# WS2812B.net
KiCad netlist of a schematic drawn in EAGLE
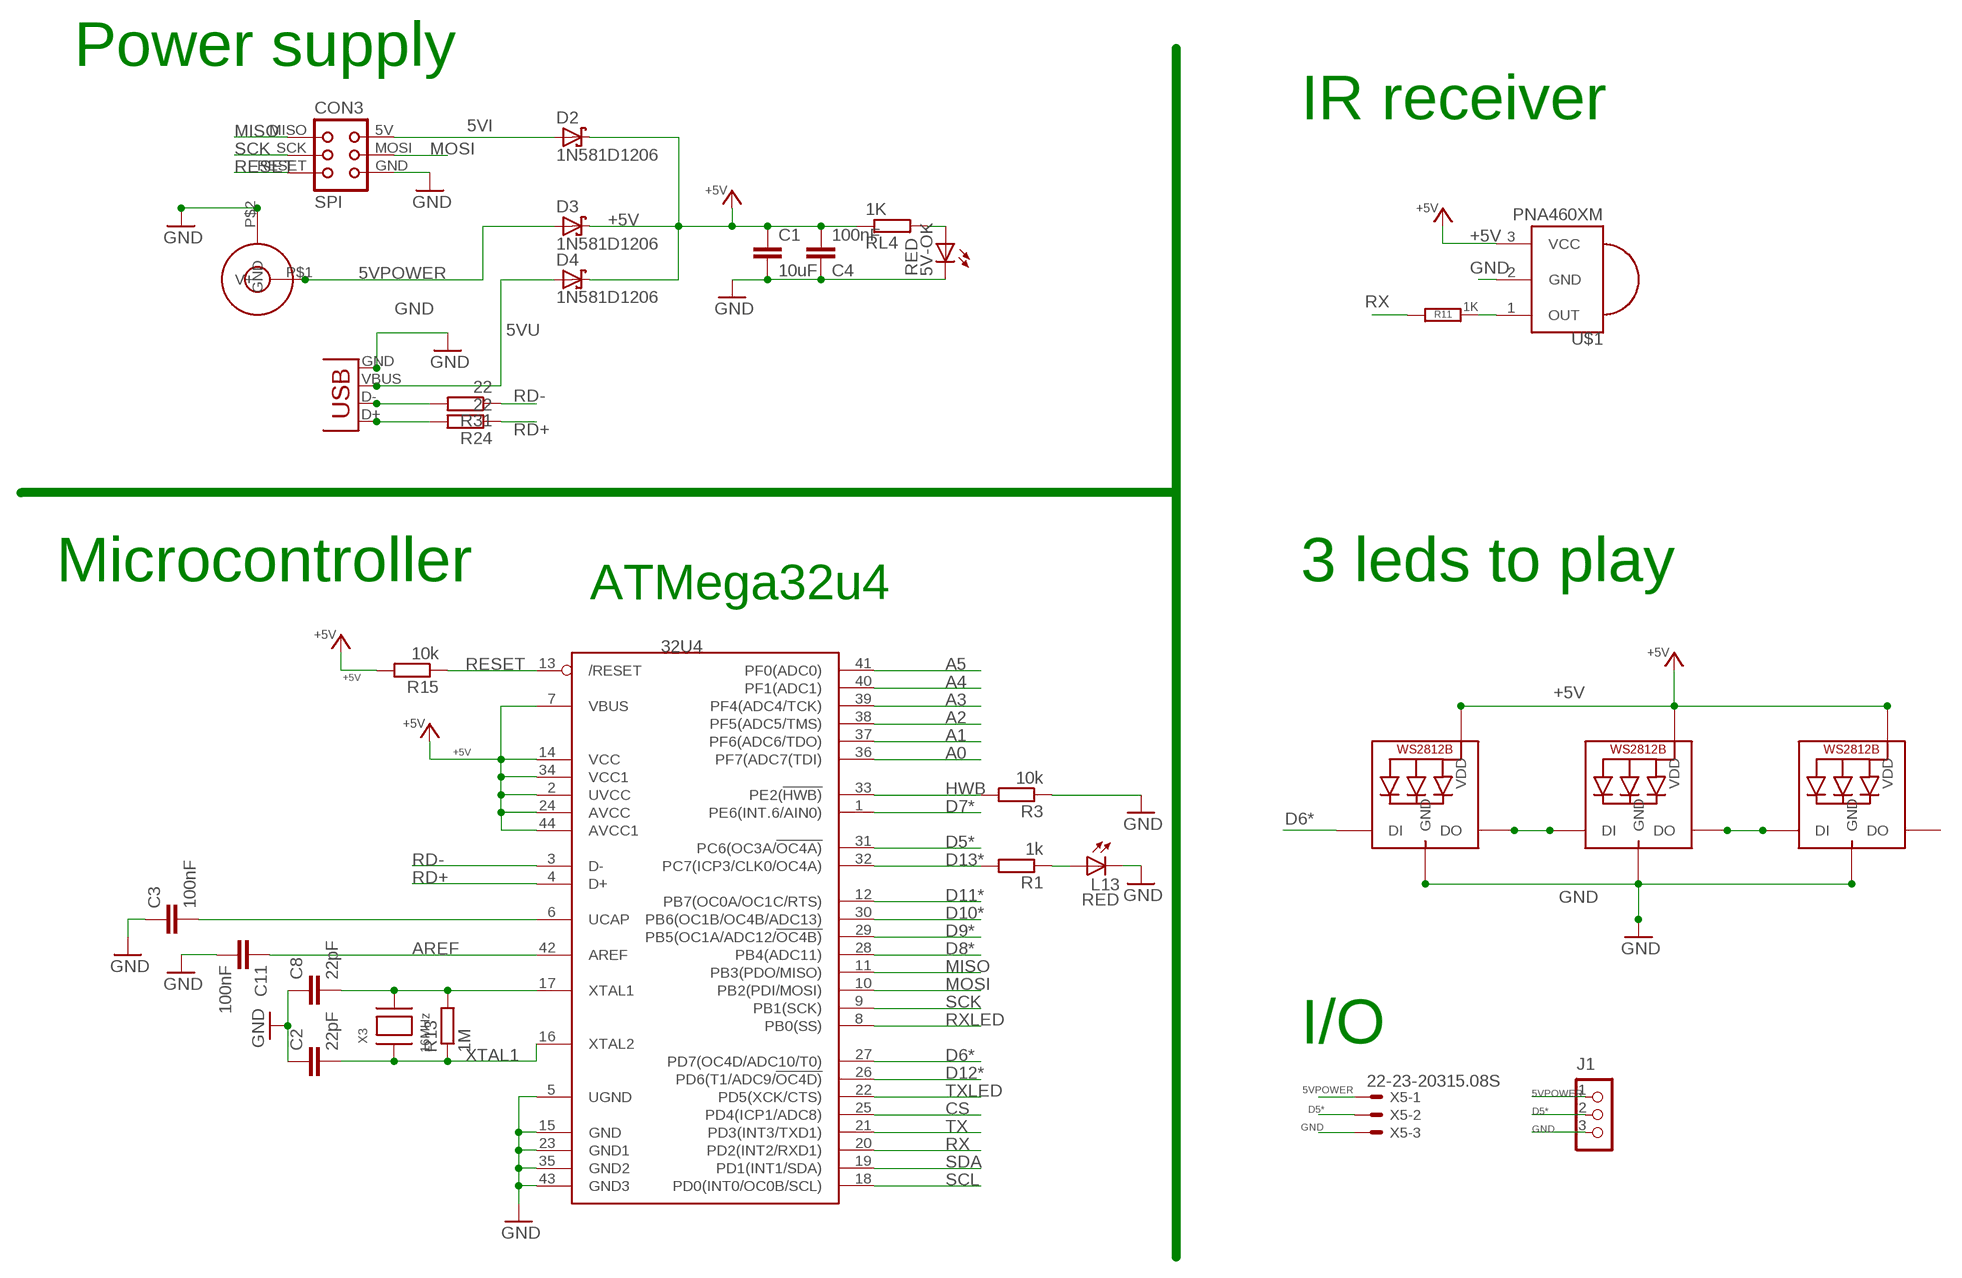
[diagram p0: schematic, sheet 1]

(export (version "E")
  (design (tool "Eeschema 10.0.6"))
  (components
    (comp (ref "5V-OK")
      (value "RED")
      (footprint "eagle-import:CHIP-LED0805")
      (libsource (lib "eagle-import") (part "LEDCHIP-LED0805"))
    )
    (comp (ref "C1")
      (value "10uF")
      (footprint "eagle-import:C1206")
      (libsource (lib "eagle-import") (part "C-EUC1206"))
    )
    (comp (ref "C2")
      (value "22pF")
      (footprint "eagle-import:C0805K")
      (libsource (lib "eagle-import") (part "C-EUC0805K"))
    )
    (comp (ref "C3")
      (value "100nF")
      (footprint "eagle-import:C0805K")
      (libsource (lib "eagle-import") (part "C-EUC0805K"))
    )
    (comp (ref "C4")
      (value "100nF")
      (footprint "eagle-import:C1206")
      (libsource (lib "eagle-import") (part "C-EUC1206"))
    )
    (comp (ref "C8")
      (value "22pF")
      (footprint "eagle-import:C0805K")
      (libsource (lib "eagle-import") (part "C-EUC0805K"))
    )
    (comp (ref "C11")
      (value "100nF")
      (footprint "eagle-import:C0805K")
      (libsource (lib "eagle-import") (part "C-EUC0805K"))
    )
    (comp (ref "CON2")
      (value "JACK_DC_BARREL")
      (footprint "eagle-import:DC_BARREL")
      (libsource (lib "eagle-import") (part "JACK_DC_BARREL"))
    )
    (comp (ref "CON3")
      (value "SPI")
      (footprint "eagle-import:TC2030-MCP-NL")
      (libsource (lib "eagle-import") (part "TINYISPT"))
    )
    (comp (ref "D2")
      (value "1N581D1206")
      (footprint "eagle-import:LED-1206")
      (libsource (lib "eagle-import") (part "1N581D1206"))
    )
    (comp (ref "D3")
      (value "1N581D1206")
      (footprint "eagle-import:LED-1206")
      (libsource (lib "eagle-import") (part "1N581D1206"))
    )
    (comp (ref "D4")
      (value "1N581D1206")
      (footprint "eagle-import:LED-1206")
      (libsource (lib "eagle-import") (part "1N581D1206"))
    )
    (comp (ref "J1")
      (value "CON_TERMINAL_BLOCK_03-5MM")
      (footprint "eagle-import:TERMINAL_BLOCK_3P_5")
      (libsource (lib "eagle-import") (part "CON_TERMINAL_BLOCK_03-5MM"))
    )
    (comp (ref "L13")
      (value "RED")
      (footprint "eagle-import:CHIP-LED0805")
      (libsource (lib "eagle-import") (part "LEDCHIP-LED0805"))
    )
    (comp (ref "LED1")
      (value "WS2812B_5050N")
      (footprint "eagle-import:WS2812B-NARROW")
      (libsource (lib "eagle-import") (part "WS2812B_5050N"))
    )
    (comp (ref "LED2")
      (value "WS2812B_5050N")
      (footprint "eagle-import:WS2812B-NARROW")
      (libsource (lib "eagle-import") (part "WS2812B_5050N"))
    )
    (comp (ref "LED3")
      (value "WS2812B_5050N")
      (footprint "eagle-import:WS2812B-NARROW")
      (libsource (lib "eagle-import") (part "WS2812B_5050N"))
    )
    (comp (ref "R1")
      (value "1k")
      (footprint "eagle-import:M0805")
      (libsource (lib "eagle-import") (part "resistor_R-EU_M0805"))
    )
    (comp (ref "R3")
      (value "10k")
      (footprint "eagle-import:M0805")
      (libsource (lib "eagle-import") (part "resistor_R-EU_M0805"))
    )
    (comp (ref "R11")
      (value "1K")
      (footprint "eagle-import:R0805")
      (libsource (lib "eagle-import") (part "resistor_R-EU_R0805"))
    )
    (comp (ref "R13")
      (value "1M")
      (footprint "eagle-import:M0805")
      (libsource (lib "eagle-import") (part "R-EU_M0805"))
    )
    (comp (ref "R15")
      (value "10k")
      (footprint "eagle-import:M0805")
      (libsource (lib "eagle-import") (part "resistor_R-EU_M0805"))
    )
    (comp (ref "R24")
      (value "22")
      (footprint "eagle-import:M0805")
      (libsource (lib "eagle-import") (part "R-EU_M0805"))
    )
    (comp (ref "R31")
      (value "22")
      (footprint "eagle-import:M0805")
      (libsource (lib "eagle-import") (part "R-EU_M0805"))
    )
    (comp (ref "RL4")
      (value "1K")
      (footprint "eagle-import:R0805")
      (libsource (lib "eagle-import") (part "resistor_R-EU_R0805"))
    )
    (comp (ref "U$1")
      (value "PNA460XM")
      (footprint "eagle-import:PNA460XM")
      (libsource (lib "eagle-import") (part "PNA460XM"))
    )
    (comp (ref "U$4")
      (value "32U4")
      (footprint "eagle-import:TQFP44")
      (libsource (lib "eagle-import") (part "ATMEGA32U4-AU"))
    )
    (comp (ref "X2")
      (value "USB-MICROB")
      (footprint "eagle-import:USB-MICROB")
      (libsource (lib "eagle-import") (part "USB-MICROB"))
    )
    (comp (ref "X3")
      (value "16MHz")
      (footprint "eagle-import:NX6035")
      (libsource (lib "eagle-import") (part "XTALNX6035"))
    )
    (comp (ref "X5")
      (value "22-23-20315.08S")
      (footprint "eagle-import:3-PIN-5.08S")
      (libsource (lib "eagle-import") (part "22-23-20315.08S"))
    )
  )
  (nets
    (net (code "1") (name "+5V") (class "Default")
      (node (ref "C1") (pin "1") (pinfunction "1_1") (pintype "passive"))
      (node (ref "C4") (pin "2") (pinfunction "2_2") (pintype "passive"))
      (node (ref "D2") (pin "C") (pinfunction "C_C") (pintype "passive"))
      (node (ref "D3") (pin "C") (pinfunction "C_C") (pintype "passive"))
      (node (ref "D4") (pin "C") (pinfunction "C_C") (pintype "passive"))
      (node (ref "LED1") (pin "1-VDD") (pinfunction "VDD_1-VDD") (pintype "power_in"))
      (node (ref "LED2") (pin "1-VDD") (pinfunction "VDD_1-VDD") (pintype "power_in"))
      (node (ref "LED3") (pin "1-VDD") (pinfunction "VDD_1-VDD") (pintype "power_in"))
      (node (ref "R15") (pin "2") (pinfunction "2_2") (pintype "passive"))
      (node (ref "RL4") (pin "1") (pinfunction "1_1") (pintype "passive"))
      (node (ref "U$1") (pin "3") (pinfunction "VCC_3") (pintype "power_in"))
      (node (ref "U$4") (pin "14") (pinfunction "VCC_14") (pintype "bidirectional"))
      (node (ref "U$4") (pin "2") (pinfunction "UVCC_2") (pintype "bidirectional"))
      (node (ref "U$4") (pin "24") (pinfunction "AVCC_24") (pintype "bidirectional"))
      (node (ref "U$4") (pin "34") (pinfunction "VCC1_34") (pintype "bidirectional"))
      (node (ref "U$4") (pin "44") (pinfunction "AVCC1_44") (pintype "bidirectional"))
      (node (ref "U$4") (pin "7") (pinfunction "VBUS_7") (pintype "bidirectional"))
    )
    (net (code "2") (name "/5VI") (class "Default")
      (node (ref "CON3") (pin "5V") (pinfunction "VCC_5V") (pintype "passive"))
      (node (ref "D2") (pin "A") (pinfunction "A_A") (pintype "passive"))
    )
    (net (code "3") (name "/5VPOWER") (class "Default")
      (node (ref "CON2") (pin "P$1") (pinfunction "V+_P$1") (pintype "bidirectional"))
      (node (ref "D3") (pin "A") (pinfunction "A_A") (pintype "passive"))
      (node (ref "J1") (pin "1") (pinfunction "1_1") (pintype "bidirectional"))
      (node (ref "X5") (pin "1") (pinfunction "S_1") (pintype "passive"))
    )
    (net (code "4") (name "/5VU") (class "Default")
      (node (ref "D4") (pin "A") (pinfunction "A_A") (pintype "passive"))
      (node (ref "X2") (pin "VBUS") (pinfunction "VBUS_VBUS") (pintype "bidirectional"))
    )
    (net (code "5") (name "/A0") (class "Default")
      (node (ref "U$4") (pin "36") (pinfunction "PF7(ADC7(TDI)_36") (pintype "bidirectional"))
    )
    (net (code "6") (name "/A1") (class "Default")
      (node (ref "U$4") (pin "37") (pinfunction "PF6(ADC6/TDO)_37") (pintype "bidirectional"))
    )
    (net (code "7") (name "/A2") (class "Default")
      (node (ref "U$4") (pin "38") (pinfunction "PF5(ADC5/TMS)_38") (pintype "bidirectional"))
    )
    (net (code "8") (name "/A3") (class "Default")
      (node (ref "U$4") (pin "39") (pinfunction "PF4(ADC4/TCK)_39") (pintype "bidirectional"))
    )
    (net (code "9") (name "/A4") (class "Default")
      (node (ref "U$4") (pin "40") (pinfunction "PF1(ADC1)_40") (pintype "bidirectional"))
    )
    (net (code "10") (name "/A5") (class "Default")
      (node (ref "U$4") (pin "41") (pinfunction "PF0(ADC0)_41") (pintype "bidirectional"))
    )
    (net (code "11") (name "/AREF") (class "Default")
      (node (ref "C11") (pin "1") (pinfunction "1_1") (pintype "passive"))
      (node (ref "U$4") (pin "42") (pinfunction "AREF_42") (pintype "bidirectional"))
    )
    (net (code "12") (name "/CS") (class "Default")
      (node (ref "U$4") (pin "25") (pinfunction "PD4(ICP1/ADC8)_25") (pintype "bidirectional"))
    )
    (net (code "13") (name "/D5*") (class "Default")
      (node (ref "J1") (pin "2") (pinfunction "2_2") (pintype "bidirectional"))
      (node (ref "U$4") (pin "31") (pinfunction "PC6(OC3A/~{OC4A})_31") (pintype "bidirectional"))
      (node (ref "X5") (pin "2") (pinfunction "S_2") (pintype "passive"))
    )
    (net (code "14") (name "/D6*") (class "Default")
      (node (ref "LED1") (pin "4-DIN") (pinfunction "DI_4-DIN") (pintype "input"))
      (node (ref "U$4") (pin "27") (pinfunction "PD7(OC4D/ADC10/T0)_27") (pintype "bidirectional"))
    )
    (net (code "15") (name "/D7*") (class "Default")
      (node (ref "U$4") (pin "1") (pinfunction "PE6(INT.6/AIN0)_1") (pintype "bidirectional"))
    )
    (net (code "16") (name "/D8*") (class "Default")
      (node (ref "U$4") (pin "28") (pinfunction "PB4(ADC11)_28") (pintype "bidirectional"))
    )
    (net (code "17") (name "/D9*") (class "Default")
      (node (ref "U$4") (pin "29") (pinfunction "PB5(OC1A/ADC12/~{OC4B})_29") (pintype "bidirectional"))
    )
    (net (code "18") (name "/D10*") (class "Default")
      (node (ref "U$4") (pin "30") (pinfunction "PB6(OC1B/OC4B/ADC13)_30") (pintype "bidirectional"))
    )
    (net (code "19") (name "/D11*") (class "Default")
      (node (ref "U$4") (pin "12") (pinfunction "PB7(OC0A/OC1C/RTS)_12") (pintype "bidirectional"))
    )
    (net (code "20") (name "/D12*") (class "Default")
      (node (ref "U$4") (pin "26") (pinfunction "PD6(T1/ADC9/~{OC4D})_26") (pintype "bidirectional"))
    )
    (net (code "21") (name "/D13*") (class "Default")
      (node (ref "R1") (pin "2") (pinfunction "2_2") (pintype "passive"))
      (node (ref "U$4") (pin "32") (pinfunction "PC7(ICP3/CLK0/OC4A)_32") (pintype "bidirectional"))
    )
    (net (code "22") (name "/HWB") (class "Default")
      (node (ref "R3") (pin "2") (pinfunction "2_2") (pintype "passive"))
      (node (ref "U$4") (pin "33") (pinfunction "PE2(~{HWB})_33") (pintype "bidirectional"))
    )
    (net (code "23") (name "/MISO") (class "Default")
      (node (ref "CON3") (pin "MISO") (pinfunction "MISO_MISO") (pintype "passive"))
      (node (ref "U$4") (pin "11") (pinfunction "PB3(PDO/MISO)_11") (pintype "bidirectional"))
    )
    (net (code "24") (name "/MOSI") (class "Default")
      (node (ref "CON3") (pin "MOSI") (pinfunction "MOSI_MOSI") (pintype "passive"))
      (node (ref "U$4") (pin "10") (pinfunction "PB2(PDI/MOSI)_10") (pintype "bidirectional"))
    )
    (net (code "25") (name "/RD+") (class "Default")
      (node (ref "R24") (pin "1") (pinfunction "1_1") (pintype "passive"))
      (node (ref "U$4") (pin "4") (pinfunction "D+_4") (pintype "bidirectional"))
    )
    (net (code "26") (name "/RD-") (class "Default")
      (node (ref "R31") (pin "1") (pinfunction "1_1") (pintype "passive"))
      (node (ref "U$4") (pin "3") (pinfunction "D-_3") (pintype "bidirectional"))
    )
    (net (code "27") (name "/RESET") (class "Default")
      (node (ref "CON3") (pin "RESET") (pinfunction "RESET_RESET") (pintype "passive"))
      (node (ref "R15") (pin "1") (pinfunction "1_1") (pintype "passive"))
      (node (ref "U$4") (pin "13") (pinfunction "/RESET_13") (pintype "bidirectional"))
    )
    (net (code "28") (name "/RX") (class "Default")
      (node (ref "R11") (pin "2") (pinfunction "2_2") (pintype "passive"))
      (node (ref "U$4") (pin "20") (pinfunction "PD2(INT2/RXD1)_20") (pintype "bidirectional"))
    )
    (net (code "29") (name "/RXLED") (class "Default")
      (node (ref "U$4") (pin "8") (pinfunction "PB0(SS)_8") (pintype "bidirectional"))
    )
    (net (code "30") (name "/SCK") (class "Default")
      (node (ref "CON3") (pin "SCK") (pinfunction "SCK_SCK") (pintype "passive"))
      (node (ref "U$4") (pin "9") (pinfunction "PB1(SCK)_9") (pintype "bidirectional"))
    )
    (net (code "31") (name "/SCL") (class "Default")
      (node (ref "U$4") (pin "18") (pinfunction "PD0(INT0/OC0B/SCL)_18") (pintype "bidirectional"))
    )
    (net (code "32") (name "/SDA") (class "Default")
      (node (ref "U$4") (pin "19") (pinfunction "PD1(INT1/SDA)_19") (pintype "bidirectional"))
    )
    (net (code "33") (name "/TX") (class "Default")
      (node (ref "U$4") (pin "21") (pinfunction "PD3(INT3/TXD1)_21") (pintype "bidirectional"))
    )
    (net (code "34") (name "/TXLED") (class "Default")
      (node (ref "U$4") (pin "22") (pinfunction "PD5(XCK/CTS)_22") (pintype "bidirectional"))
    )
    (net (code "35") (name "/XTAL1") (class "Default")
      (node (ref "C2") (pin "2") (pinfunction "2_2") (pintype "passive"))
      (node (ref "R13") (pin "1") (pinfunction "1_1") (pintype "passive"))
      (node (ref "U$4") (pin "16") (pinfunction "XTAL2_16") (pintype "bidirectional"))
      (node (ref "X3") (pin "P$1") (pinfunction "P$1_P$1") (pintype "bidirectional"))
    )
    (net (code "36") (name "GND") (class "Default")
      (node (ref "5V-OK") (pin "C") (pinfunction "C_C") (pintype "passive"))
      (node (ref "C1") (pin "2") (pinfunction "2_2") (pintype "passive"))
      (node (ref "C11") (pin "2") (pinfunction "2_2") (pintype "passive"))
      (node (ref "C2") (pin "1") (pinfunction "1_1") (pintype "passive"))
      (node (ref "C3") (pin "1") (pinfunction "1_1") (pintype "passive"))
      (node (ref "C4") (pin "1") (pinfunction "1_1") (pintype "passive"))
      (node (ref "C8") (pin "1") (pinfunction "1_1") (pintype "passive"))
      (node (ref "CON2") (pin "P$2") (pinfunction "GND_P$2") (pintype "bidirectional"))
      (node (ref "CON3") (pin "GND") (pinfunction "GND_GND") (pintype "passive"))
      (node (ref "J1") (pin "3") (pinfunction "3_3") (pintype "bidirectional"))
      (node (ref "L13") (pin "C") (pinfunction "C_C") (pintype "passive"))
      (node (ref "LED1") (pin "3-GND") (pinfunction "GND_3-GND") (pintype "power_in"))
      (node (ref "LED2") (pin "3-GND") (pinfunction "GND_3-GND") (pintype "power_in"))
      (node (ref "LED3") (pin "3-GND") (pinfunction "GND_3-GND") (pintype "power_in"))
      (node (ref "R3") (pin "1") (pinfunction "1_1") (pintype "passive"))
      (node (ref "U$1") (pin "2") (pinfunction "GND_2") (pintype "power_in"))
      (node (ref "U$4") (pin "15") (pinfunction "GND_15") (pintype "bidirectional"))
      (node (ref "U$4") (pin "23") (pinfunction "GND1_23") (pintype "bidirectional"))
      (node (ref "U$4") (pin "35") (pinfunction "GND2_35") (pintype "bidirectional"))
      (node (ref "U$4") (pin "43") (pinfunction "GND3_43") (pintype "bidirectional"))
      (node (ref "U$4") (pin "5") (pinfunction "UGND_5") (pintype "bidirectional"))
      (node (ref "X2") (pin "GND") (pinfunction "GND_GND") (pintype "bidirectional"))
      (node (ref "X5") (pin "3") (pinfunction "S_3") (pintype "passive"))
    )
    (net (code "37") (name "Net-(5V-OK-PadA)") (class "Default")
      (node (ref "5V-OK") (pin "A") (pinfunction "A_A") (pintype "passive"))
      (node (ref "RL4") (pin "2") (pinfunction "2_2") (pintype "passive"))
    )
    (net (code "38") (name "Net-(L13-PadA)") (class "Default")
      (node (ref "L13") (pin "A") (pinfunction "A_A") (pintype "passive"))
      (node (ref "R1") (pin "1") (pinfunction "1_1") (pintype "passive"))
    )
    (net (code "39") (name "Net-(LED1-DO)") (class "Default")
      (node (ref "LED1") (pin "2-DOUT") (pinfunction "DO_2-DOUT") (pintype "output"))
      (node (ref "LED2") (pin "4-DIN") (pinfunction "DI_4-DIN") (pintype "input"))
    )
    (net (code "40") (name "Net-(LED2-DO)") (class "Default")
      (node (ref "LED2") (pin "2-DOUT") (pinfunction "DO_2-DOUT") (pintype "output"))
      (node (ref "LED3") (pin "4-DIN") (pinfunction "DI_4-DIN") (pintype "input"))
    )
    (net (code "41") (name "Net-(R24-Pad2)") (class "Default")
      (node (ref "R24") (pin "2") (pinfunction "2_2") (pintype "passive"))
      (node (ref "X2") (pin "D+") (pinfunction "D+_D+") (pintype "bidirectional"))
    )
    (net (code "42") (name "Net-(R31-Pad2)") (class "Default")
      (node (ref "R31") (pin "2") (pinfunction "2_2") (pintype "passive"))
      (node (ref "X2") (pin "D-") (pinfunction "D-_D-") (pintype "bidirectional"))
    )
    (net (code "43") (name "Net-(U$1-OUT)") (class "Default")
      (node (ref "R11") (pin "1") (pinfunction "1_1") (pintype "passive"))
      (node (ref "U$1") (pin "1") (pinfunction "OUT_1") (pintype "output"))
    )
    (net (code "44") (name "Net-(U$4-UCAP)") (class "Default")
      (node (ref "C3") (pin "2") (pinfunction "2_2") (pintype "passive"))
      (node (ref "U$4") (pin "6") (pinfunction "UCAP_6") (pintype "bidirectional"))
    )
    (net (code "45") (name "Net-(U$4-XTAL1)") (class "Default")
      (node (ref "C8") (pin "2") (pinfunction "2_2") (pintype "passive"))
      (node (ref "R13") (pin "2") (pinfunction "2_2") (pintype "passive"))
      (node (ref "U$4") (pin "17") (pinfunction "XTAL1_17") (pintype "bidirectional"))
      (node (ref "X3") (pin "P$2") (pinfunction "P$2_P$2") (pintype "bidirectional"))
    )
    (net (code "46") (name "unconnected-(LED3-DO-Pad2-DOUT)") (class "Default")
      (node (ref "LED3") (pin "2-DOUT") (pinfunction "DO_2-DOUT") (pintype "output"))
    )
  )
)
